# Teensy_Board_Connectors.net
KiCad netlist of a schematic drawn in EAGLE
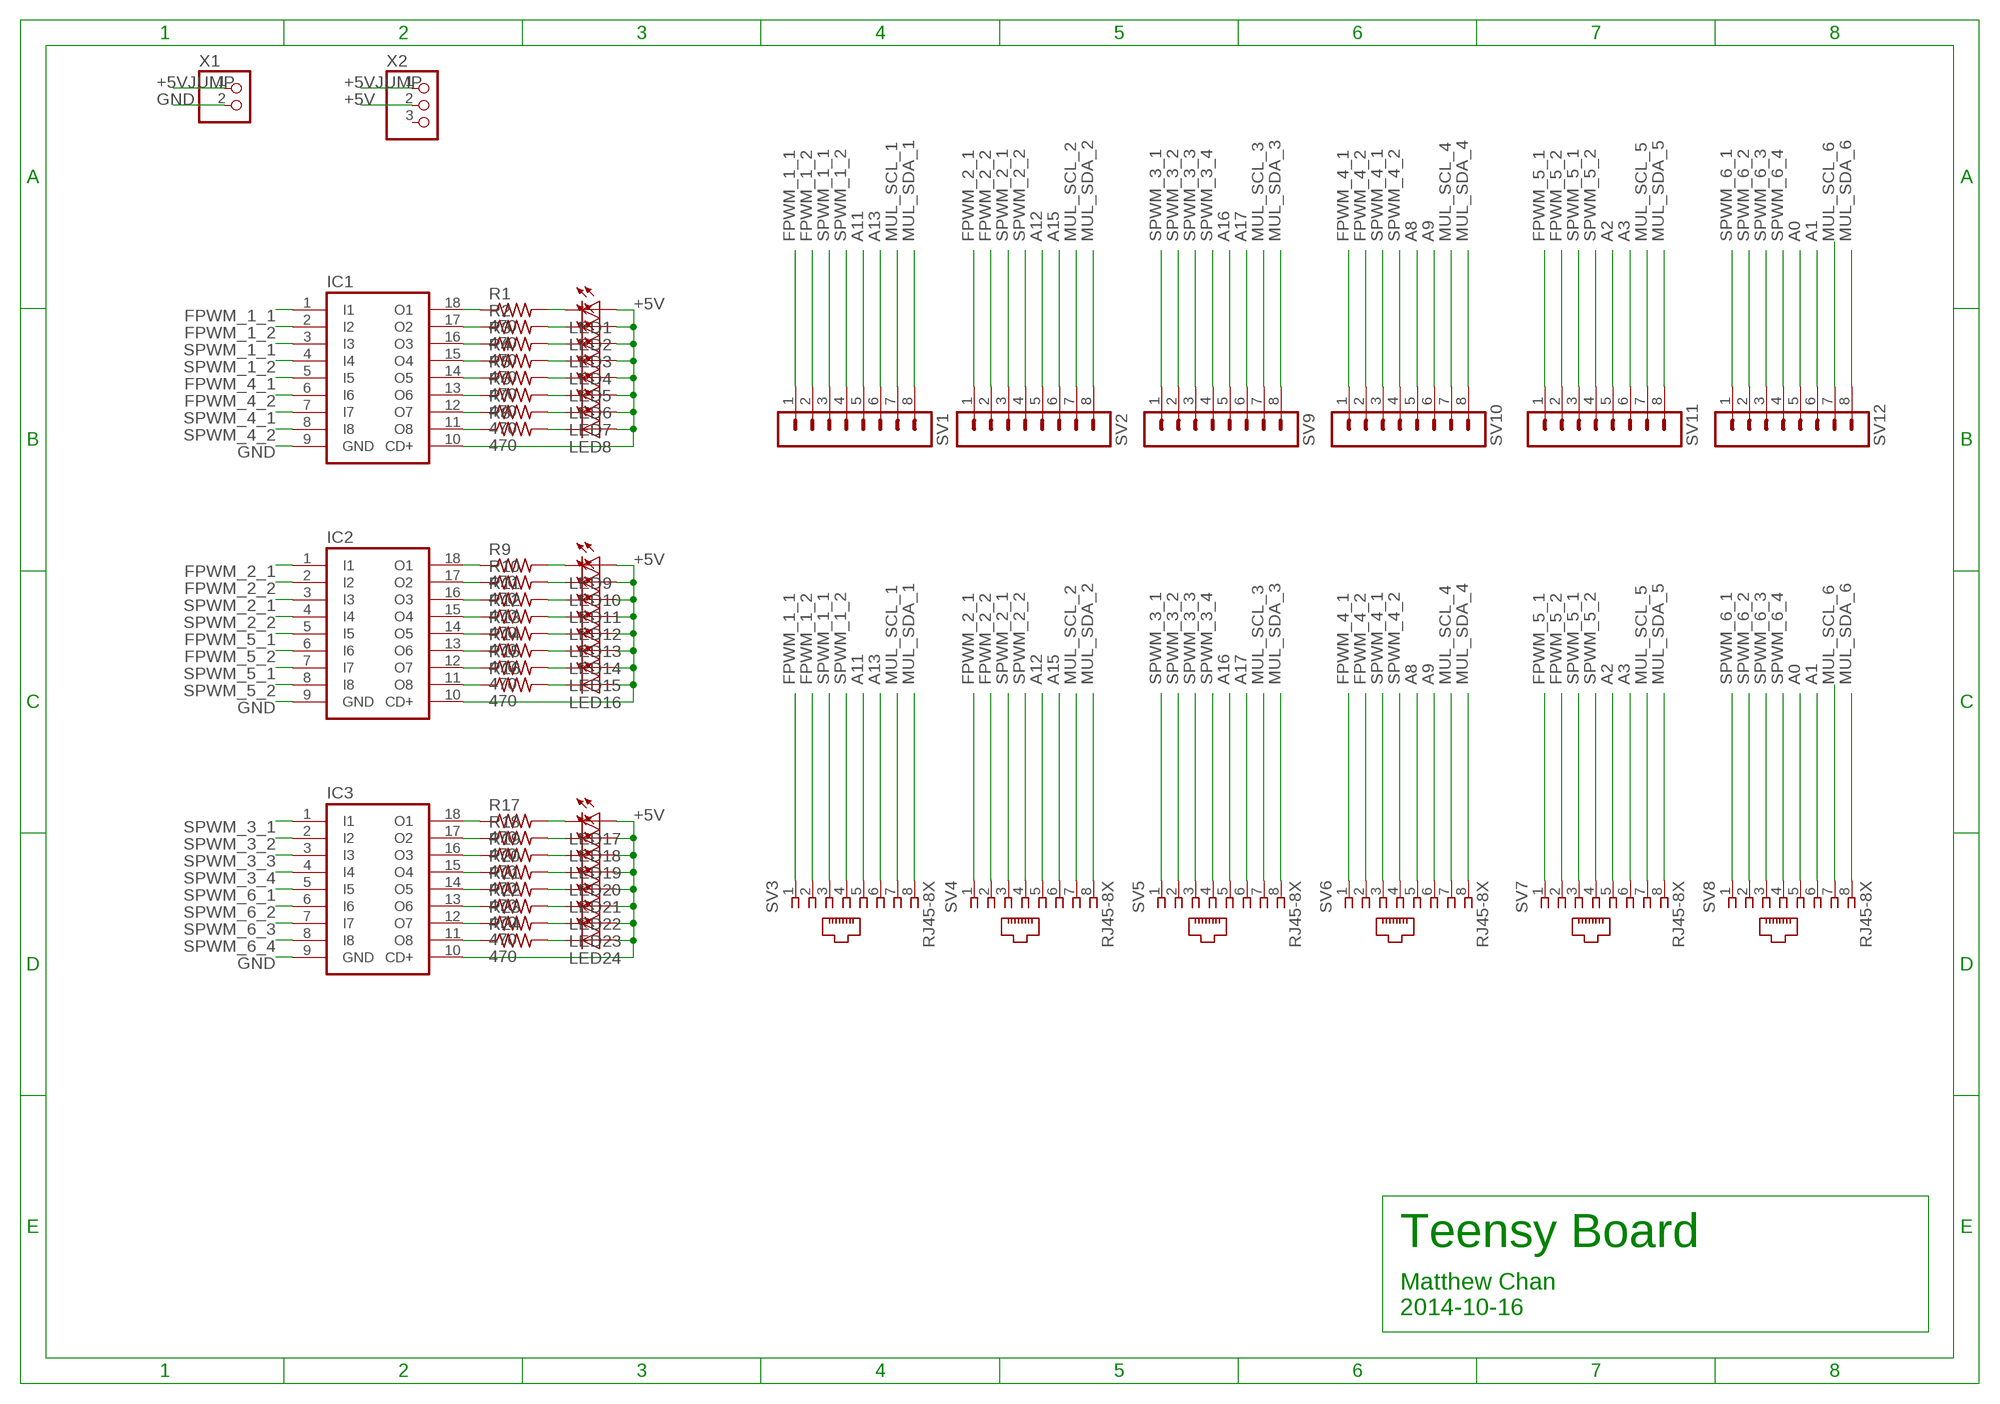
[diagram p0: schematic, sheet 1]

(export (version "E")
  (design (tool "Eeschema 10.0.6"))
  (components
    (comp (ref "IC1")
      (value "ULN2803AFWG")
      (footprint "eagle-import:SOP18")
      (libsource (lib "eagle-import") (part "ULN2803AFWG"))
    )
    (comp (ref "IC2")
      (value "ULN2803AFWG")
      (footprint "eagle-import:SOP18")
      (libsource (lib "eagle-import") (part "ULN2803AFWG"))
    )
    (comp (ref "IC3")
      (value "ULN2803AFWG")
      (footprint "eagle-import:SOP18")
      (libsource (lib "eagle-import") (part "ULN2803AFWG"))
    )
    (comp (ref "LED1")
      (value "LEDSML1206")
      (footprint "eagle-import:SML1206")
      (libsource (lib "eagle-import") (part "LEDSML1206"))
    )
    (comp (ref "LED2")
      (value "LEDSML1206")
      (footprint "eagle-import:SML1206")
      (libsource (lib "eagle-import") (part "LEDSML1206"))
    )
    (comp (ref "LED3")
      (value "LEDSML1206")
      (footprint "eagle-import:SML1206")
      (libsource (lib "eagle-import") (part "LEDSML1206"))
    )
    (comp (ref "LED4")
      (value "LEDSML1206")
      (footprint "eagle-import:SML1206")
      (libsource (lib "eagle-import") (part "LEDSML1206"))
    )
    (comp (ref "LED5")
      (value "LEDSML1206")
      (footprint "eagle-import:SML1206")
      (libsource (lib "eagle-import") (part "LEDSML1206"))
    )
    (comp (ref "LED6")
      (value "LEDSML1206")
      (footprint "eagle-import:SML1206")
      (libsource (lib "eagle-import") (part "LEDSML1206"))
    )
    (comp (ref "LED7")
      (value "LEDSML1206")
      (footprint "eagle-import:SML1206")
      (libsource (lib "eagle-import") (part "LEDSML1206"))
    )
    (comp (ref "LED8")
      (value "LEDSML1206")
      (footprint "eagle-import:SML1206")
      (libsource (lib "eagle-import") (part "LEDSML1206"))
    )
    (comp (ref "LED9")
      (value "LEDSML1206")
      (footprint "eagle-import:SML1206")
      (libsource (lib "eagle-import") (part "LEDSML1206"))
    )
    (comp (ref "LED10")
      (value "LEDSML1206")
      (footprint "eagle-import:SML1206")
      (libsource (lib "eagle-import") (part "LEDSML1206"))
    )
    (comp (ref "LED11")
      (value "LEDSML1206")
      (footprint "eagle-import:SML1206")
      (libsource (lib "eagle-import") (part "LEDSML1206"))
    )
    (comp (ref "LED12")
      (value "LEDSML1206")
      (footprint "eagle-import:SML1206")
      (libsource (lib "eagle-import") (part "LEDSML1206"))
    )
    (comp (ref "LED13")
      (value "LEDSML1206")
      (footprint "eagle-import:SML1206")
      (libsource (lib "eagle-import") (part "LEDSML1206"))
    )
    (comp (ref "LED14")
      (value "LEDSML1206")
      (footprint "eagle-import:SML1206")
      (libsource (lib "eagle-import") (part "LEDSML1206"))
    )
    (comp (ref "LED15")
      (value "LEDSML1206")
      (footprint "eagle-import:SML1206")
      (libsource (lib "eagle-import") (part "LEDSML1206"))
    )
    (comp (ref "LED16")
      (value "LEDSML1206")
      (footprint "eagle-import:SML1206")
      (libsource (lib "eagle-import") (part "LEDSML1206"))
    )
    (comp (ref "LED17")
      (value "LEDSML1206")
      (footprint "eagle-import:SML1206")
      (libsource (lib "eagle-import") (part "LEDSML1206"))
    )
    (comp (ref "LED18")
      (value "LEDSML1206")
      (footprint "eagle-import:SML1206")
      (libsource (lib "eagle-import") (part "LEDSML1206"))
    )
    (comp (ref "LED19")
      (value "LEDSML1206")
      (footprint "eagle-import:SML1206")
      (libsource (lib "eagle-import") (part "LEDSML1206"))
    )
    (comp (ref "LED20")
      (value "LEDSML1206")
      (footprint "eagle-import:SML1206")
      (libsource (lib "eagle-import") (part "LEDSML1206"))
    )
    (comp (ref "LED21")
      (value "LEDSML1206")
      (footprint "eagle-import:SML1206")
      (libsource (lib "eagle-import") (part "LEDSML1206"))
    )
    (comp (ref "LED22")
      (value "LEDSML1206")
      (footprint "eagle-import:SML1206")
      (libsource (lib "eagle-import") (part "LEDSML1206"))
    )
    (comp (ref "LED23")
      (value "LEDSML1206")
      (footprint "eagle-import:SML1206")
      (libsource (lib "eagle-import") (part "LEDSML1206"))
    )
    (comp (ref "LED24")
      (value "LEDSML1206")
      (footprint "eagle-import:SML1206")
      (libsource (lib "eagle-import") (part "LEDSML1206"))
    )
    (comp (ref "R1")
      (value "470")
      (footprint "eagle-import:R0603")
      (libsource (lib "eagle-import") (part "R-US_R0603"))
    )
    (comp (ref "R2")
      (value "470")
      (footprint "eagle-import:R0603")
      (libsource (lib "eagle-import") (part "R-US_R0603"))
    )
    (comp (ref "R3")
      (value "470")
      (footprint "eagle-import:R0603")
      (libsource (lib "eagle-import") (part "R-US_R0603"))
    )
    (comp (ref "R4")
      (value "470")
      (footprint "eagle-import:R0603")
      (libsource (lib "eagle-import") (part "R-US_R0603"))
    )
    (comp (ref "R5")
      (value "470")
      (footprint "eagle-import:R0603")
      (libsource (lib "eagle-import") (part "R-US_R0603"))
    )
    (comp (ref "R6")
      (value "470")
      (footprint "eagle-import:R0603")
      (libsource (lib "eagle-import") (part "R-US_R0603"))
    )
    (comp (ref "R7")
      (value "470")
      (footprint "eagle-import:R0603")
      (libsource (lib "eagle-import") (part "R-US_R0603"))
    )
    (comp (ref "R8")
      (value "470")
      (footprint "eagle-import:R0603")
      (libsource (lib "eagle-import") (part "R-US_R0603"))
    )
    (comp (ref "R9")
      (value "470")
      (footprint "eagle-import:R0603")
      (libsource (lib "eagle-import") (part "R-US_R0603"))
    )
    (comp (ref "R10")
      (value "470")
      (footprint "eagle-import:R0603")
      (libsource (lib "eagle-import") (part "R-US_R0603"))
    )
    (comp (ref "R11")
      (value "470")
      (footprint "eagle-import:R0603")
      (libsource (lib "eagle-import") (part "R-US_R0603"))
    )
    (comp (ref "R12")
      (value "470")
      (footprint "eagle-import:R0603")
      (libsource (lib "eagle-import") (part "R-US_R0603"))
    )
    (comp (ref "R13")
      (value "470")
      (footprint "eagle-import:R0603")
      (libsource (lib "eagle-import") (part "R-US_R0603"))
    )
    (comp (ref "R14")
      (value "470")
      (footprint "eagle-import:R0603")
      (libsource (lib "eagle-import") (part "R-US_R0603"))
    )
    (comp (ref "R15")
      (value "470")
      (footprint "eagle-import:R0603")
      (libsource (lib "eagle-import") (part "R-US_R0603"))
    )
    (comp (ref "R16")
      (value "470")
      (footprint "eagle-import:R0603")
      (libsource (lib "eagle-import") (part "R-US_R0603"))
    )
    (comp (ref "R17")
      (value "470")
      (footprint "eagle-import:R0603")
      (libsource (lib "eagle-import") (part "R-US_R0603"))
    )
    (comp (ref "R18")
      (value "470")
      (footprint "eagle-import:R0603")
      (libsource (lib "eagle-import") (part "R-US_R0603"))
    )
    (comp (ref "R19")
      (value "470")
      (footprint "eagle-import:R0603")
      (libsource (lib "eagle-import") (part "R-US_R0603"))
    )
    (comp (ref "R20")
      (value "470")
      (footprint "eagle-import:R0603")
      (libsource (lib "eagle-import") (part "R-US_R0603"))
    )
    (comp (ref "R21")
      (value "470")
      (footprint "eagle-import:R0603")
      (libsource (lib "eagle-import") (part "R-US_R0603"))
    )
    (comp (ref "R22")
      (value "470")
      (footprint "eagle-import:R0603")
      (libsource (lib "eagle-import") (part "R-US_R0603"))
    )
    (comp (ref "R23")
      (value "470")
      (footprint "eagle-import:R0603")
      (libsource (lib "eagle-import") (part "R-US_R0603"))
    )
    (comp (ref "R24")
      (value "470")
      (footprint "eagle-import:R0603")
      (libsource (lib "eagle-import") (part "R-US_R0603"))
    )
    (comp (ref "SV1")
      (value "MA08-1")
      (footprint "eagle-import:MA08-1")
      (libsource (lib "eagle-import") (part "MA08-1"))
    )
    (comp (ref "SV2")
      (value "MA08-1")
      (footprint "eagle-import:MA08-1")
      (libsource (lib "eagle-import") (part "MA08-1"))
    )
    (comp (ref "SV3")
      (value "RJ45-8X")
      (footprint "eagle-import:RJ45-NO-SHIELD")
      (libsource (lib "eagle-import") (part "RJ45-8X"))
    )
    (comp (ref "SV4")
      (value "RJ45-8X")
      (footprint "eagle-import:RJ45-NO-SHIELD")
      (libsource (lib "eagle-import") (part "RJ45-8X"))
    )
    (comp (ref "SV5")
      (value "RJ45-8X")
      (footprint "eagle-import:RJ45-NO-SHIELD")
      (libsource (lib "eagle-import") (part "RJ45-8X"))
    )
    (comp (ref "SV6")
      (value "RJ45-8X")
      (footprint "eagle-import:RJ45-NO-SHIELD")
      (libsource (lib "eagle-import") (part "RJ45-8X"))
    )
    (comp (ref "SV7")
      (value "RJ45-8X")
      (footprint "eagle-import:RJ45-NO-SHIELD")
      (libsource (lib "eagle-import") (part "RJ45-8X"))
    )
    (comp (ref "SV8")
      (value "RJ45-8X")
      (footprint "eagle-import:RJ45-NO-SHIELD")
      (libsource (lib "eagle-import") (part "RJ45-8X"))
    )
    (comp (ref "SV9")
      (value "MA08-1")
      (footprint "eagle-import:MA08-1")
      (libsource (lib "eagle-import") (part "MA08-1"))
    )
    (comp (ref "SV10")
      (value "MA08-1")
      (footprint "eagle-import:MA08-1")
      (libsource (lib "eagle-import") (part "MA08-1"))
    )
    (comp (ref "SV11")
      (value "MA08-1")
      (footprint "eagle-import:MA08-1")
      (libsource (lib "eagle-import") (part "MA08-1"))
    )
    (comp (ref "SV12")
      (value "MA08-1")
      (footprint "eagle-import:MA08-1")
      (libsource (lib "eagle-import") (part "MA08-1"))
    )
    (comp (ref "X1")
      (value "PINHD-1X2")
      (footprint "eagle-import:1X02")
      (libsource (lib "eagle-import") (part "PINHD-1X2"))
    )
    (comp (ref "X2")
      (value "PINHD-1X3")
      (footprint "eagle-import:1X03")
      (libsource (lib "eagle-import") (part "PINHD-1X3"))
    )
  )
  (nets
    (net (code "1") (name "/+5V") (class "Default")
      (node (ref "IC1") (pin "10") (pinfunction "CD+_10") (pintype "passive"))
      (node (ref "IC2") (pin "10") (pinfunction "CD+_10") (pintype "passive"))
      (node (ref "IC3") (pin "10") (pinfunction "CD+_10") (pintype "passive"))
      (node (ref "LED1") (pin "A") (pinfunction "A_A") (pintype "passive"))
      (node (ref "LED10") (pin "A") (pinfunction "A_A") (pintype "passive"))
      (node (ref "LED11") (pin "A") (pinfunction "A_A") (pintype "passive"))
      (node (ref "LED12") (pin "A") (pinfunction "A_A") (pintype "passive"))
      (node (ref "LED13") (pin "A") (pinfunction "A_A") (pintype "passive"))
      (node (ref "LED14") (pin "A") (pinfunction "A_A") (pintype "passive"))
      (node (ref "LED15") (pin "A") (pinfunction "A_A") (pintype "passive"))
      (node (ref "LED16") (pin "A") (pinfunction "A_A") (pintype "passive"))
      (node (ref "LED17") (pin "A") (pinfunction "A_A") (pintype "passive"))
      (node (ref "LED18") (pin "A") (pinfunction "A_A") (pintype "passive"))
      (node (ref "LED19") (pin "A") (pinfunction "A_A") (pintype "passive"))
      (node (ref "LED2") (pin "A") (pinfunction "A_A") (pintype "passive"))
      (node (ref "LED20") (pin "A") (pinfunction "A_A") (pintype "passive"))
      (node (ref "LED21") (pin "A") (pinfunction "A_A") (pintype "passive"))
      (node (ref "LED22") (pin "A") (pinfunction "A_A") (pintype "passive"))
      (node (ref "LED23") (pin "A") (pinfunction "A_A") (pintype "passive"))
      (node (ref "LED24") (pin "A") (pinfunction "A_A") (pintype "passive"))
      (node (ref "LED3") (pin "A") (pinfunction "A_A") (pintype "passive"))
      (node (ref "LED4") (pin "A") (pinfunction "A_A") (pintype "passive"))
      (node (ref "LED5") (pin "A") (pinfunction "A_A") (pintype "passive"))
      (node (ref "LED6") (pin "A") (pinfunction "A_A") (pintype "passive"))
      (node (ref "LED7") (pin "A") (pinfunction "A_A") (pintype "passive"))
      (node (ref "LED8") (pin "A") (pinfunction "A_A") (pintype "passive"))
      (node (ref "LED9") (pin "A") (pinfunction "A_A") (pintype "passive"))
      (node (ref "X2") (pin "2") (pinfunction "2_2") (pintype "passive"))
    )
    (net (code "2") (name "/+5VJUMP") (class "Default")
      (node (ref "X1") (pin "1") (pinfunction "1_1") (pintype "passive"))
      (node (ref "X2") (pin "1") (pinfunction "1_1") (pintype "passive"))
    )
    (net (code "3") (name "/A0") (class "Default")
      (node (ref "SV12") (pin "5") (pinfunction "5_5") (pintype "passive"))
      (node (ref "SV8") (pin "5") (pinfunction "5_5") (pintype "passive"))
    )
    (net (code "4") (name "/A1") (class "Default")
      (node (ref "SV12") (pin "6") (pinfunction "6_6") (pintype "passive"))
      (node (ref "SV8") (pin "6") (pinfunction "6_6") (pintype "passive"))
    )
    (net (code "5") (name "/A2") (class "Default")
      (node (ref "SV11") (pin "5") (pinfunction "5_5") (pintype "passive"))
      (node (ref "SV7") (pin "5") (pinfunction "5_5") (pintype "passive"))
    )
    (net (code "6") (name "/A3") (class "Default")
      (node (ref "SV11") (pin "6") (pinfunction "6_6") (pintype "passive"))
      (node (ref "SV7") (pin "6") (pinfunction "6_6") (pintype "passive"))
    )
    (net (code "7") (name "/A8") (class "Default")
      (node (ref "SV10") (pin "5") (pinfunction "5_5") (pintype "passive"))
      (node (ref "SV6") (pin "5") (pinfunction "5_5") (pintype "passive"))
    )
    (net (code "8") (name "/A9") (class "Default")
      (node (ref "SV10") (pin "6") (pinfunction "6_6") (pintype "passive"))
      (node (ref "SV6") (pin "6") (pinfunction "6_6") (pintype "passive"))
    )
    (net (code "9") (name "/A11") (class "Default")
      (node (ref "SV1") (pin "5") (pinfunction "5_5") (pintype "passive"))
      (node (ref "SV3") (pin "5") (pinfunction "5_5") (pintype "passive"))
    )
    (net (code "10") (name "/A12") (class "Default")
      (node (ref "SV2") (pin "5") (pinfunction "5_5") (pintype "passive"))
      (node (ref "SV4") (pin "5") (pinfunction "5_5") (pintype "passive"))
    )
    (net (code "11") (name "/A13") (class "Default")
      (node (ref "SV1") (pin "6") (pinfunction "6_6") (pintype "passive"))
      (node (ref "SV3") (pin "6") (pinfunction "6_6") (pintype "passive"))
    )
    (net (code "12") (name "/A15") (class "Default")
      (node (ref "SV2") (pin "6") (pinfunction "6_6") (pintype "passive"))
      (node (ref "SV4") (pin "6") (pinfunction "6_6") (pintype "passive"))
    )
    (net (code "13") (name "/A16") (class "Default")
      (node (ref "SV5") (pin "5") (pinfunction "5_5") (pintype "passive"))
      (node (ref "SV9") (pin "5") (pinfunction "5_5") (pintype "passive"))
    )
    (net (code "14") (name "/A17") (class "Default")
      (node (ref "SV5") (pin "6") (pinfunction "6_6") (pintype "passive"))
      (node (ref "SV9") (pin "6") (pinfunction "6_6") (pintype "passive"))
    )
    (net (code "15") (name "/FPWM_1_1") (class "Default")
      (node (ref "IC1") (pin "1") (pinfunction "I1_1") (pintype "input"))
      (node (ref "SV1") (pin "1") (pinfunction "1_1") (pintype "passive"))
      (node (ref "SV3") (pin "1") (pinfunction "1_1") (pintype "passive"))
    )
    (net (code "16") (name "/FPWM_1_2") (class "Default")
      (node (ref "IC1") (pin "2") (pinfunction "I2_2") (pintype "input"))
      (node (ref "SV1") (pin "2") (pinfunction "2_2") (pintype "passive"))
      (node (ref "SV3") (pin "2") (pinfunction "2_2") (pintype "passive"))
    )
    (net (code "17") (name "/FPWM_2_1") (class "Default")
      (node (ref "IC2") (pin "1") (pinfunction "I1_1") (pintype "input"))
      (node (ref "SV2") (pin "1") (pinfunction "1_1") (pintype "passive"))
      (node (ref "SV4") (pin "1") (pinfunction "1_1") (pintype "passive"))
    )
    (net (code "18") (name "/FPWM_2_2") (class "Default")
      (node (ref "IC2") (pin "2") (pinfunction "I2_2") (pintype "input"))
      (node (ref "SV2") (pin "2") (pinfunction "2_2") (pintype "passive"))
      (node (ref "SV4") (pin "2") (pinfunction "2_2") (pintype "passive"))
    )
    (net (code "19") (name "/FPWM_4_1") (class "Default")
      (node (ref "IC1") (pin "5") (pinfunction "I5_5") (pintype "input"))
      (node (ref "SV10") (pin "1") (pinfunction "1_1") (pintype "passive"))
      (node (ref "SV6") (pin "1") (pinfunction "1_1") (pintype "passive"))
    )
    (net (code "20") (name "/FPWM_4_2") (class "Default")
      (node (ref "IC1") (pin "6") (pinfunction "I6_6") (pintype "input"))
      (node (ref "SV10") (pin "2") (pinfunction "2_2") (pintype "passive"))
      (node (ref "SV6") (pin "2") (pinfunction "2_2") (pintype "passive"))
    )
    (net (code "21") (name "/FPWM_5_1") (class "Default")
      (node (ref "IC2") (pin "5") (pinfunction "I5_5") (pintype "input"))
      (node (ref "SV11") (pin "1") (pinfunction "1_1") (pintype "passive"))
      (node (ref "SV7") (pin "1") (pinfunction "1_1") (pintype "passive"))
    )
    (net (code "22") (name "/FPWM_5_2") (class "Default")
      (node (ref "IC2") (pin "6") (pinfunction "I6_6") (pintype "input"))
      (node (ref "SV11") (pin "2") (pinfunction "2_2") (pintype "passive"))
      (node (ref "SV7") (pin "2") (pinfunction "2_2") (pintype "passive"))
    )
    (net (code "23") (name "/GND") (class "Default")
      (node (ref "IC1") (pin "9") (pinfunction "GND_9") (pintype "power_in"))
      (node (ref "IC2") (pin "9") (pinfunction "GND_9") (pintype "power_in"))
      (node (ref "IC3") (pin "9") (pinfunction "GND_9") (pintype "power_in"))
      (node (ref "X1") (pin "2") (pinfunction "2_2") (pintype "passive"))
    )
    (net (code "24") (name "/MUL_SCL_1") (class "Default")
      (node (ref "SV1") (pin "7") (pinfunction "7_7") (pintype "passive"))
      (node (ref "SV3") (pin "7") (pinfunction "7_7") (pintype "passive"))
    )
    (net (code "25") (name "/MUL_SCL_2") (class "Default")
      (node (ref "SV2") (pin "7") (pinfunction "7_7") (pintype "passive"))
      (node (ref "SV4") (pin "7") (pinfunction "7_7") (pintype "passive"))
    )
    (net (code "26") (name "/MUL_SCL_3") (class "Default")
      (node (ref "SV5") (pin "7") (pinfunction "7_7") (pintype "passive"))
      (node (ref "SV9") (pin "7") (pinfunction "7_7") (pintype "passive"))
    )
    (net (code "27") (name "/MUL_SCL_4") (class "Default")
      (node (ref "SV10") (pin "7") (pinfunction "7_7") (pintype "passive"))
      (node (ref "SV6") (pin "7") (pinfunction "7_7") (pintype "passive"))
    )
    (net (code "28") (name "/MUL_SCL_5") (class "Default")
      (node (ref "SV11") (pin "7") (pinfunction "7_7") (pintype "passive"))
      (node (ref "SV7") (pin "7") (pinfunction "7_7") (pintype "passive"))
    )
    (net (code "29") (name "/MUL_SCL_6") (class "Default")
      (node (ref "SV12") (pin "7") (pinfunction "7_7") (pintype "passive"))
      (node (ref "SV8") (pin "7") (pinfunction "7_7") (pintype "passive"))
    )
    (net (code "30") (name "/MUL_SDA_1") (class "Default")
      (node (ref "SV1") (pin "8") (pinfunction "8_8") (pintype "passive"))
      (node (ref "SV3") (pin "8") (pinfunction "8_8") (pintype "passive"))
    )
    (net (code "31") (name "/MUL_SDA_2") (class "Default")
      (node (ref "SV2") (pin "8") (pinfunction "8_8") (pintype "passive"))
      (node (ref "SV4") (pin "8") (pinfunction "8_8") (pintype "passive"))
    )
    (net (code "32") (name "/MUL_SDA_3") (class "Default")
      (node (ref "SV5") (pin "8") (pinfunction "8_8") (pintype "passive"))
      (node (ref "SV9") (pin "8") (pinfunction "8_8") (pintype "passive"))
    )
    (net (code "33") (name "/MUL_SDA_4") (class "Default")
      (node (ref "SV10") (pin "8") (pinfunction "8_8") (pintype "passive"))
      (node (ref "SV6") (pin "8") (pinfunction "8_8") (pintype "passive"))
    )
    (net (code "34") (name "/MUL_SDA_5") (class "Default")
      (node (ref "SV11") (pin "8") (pinfunction "8_8") (pintype "passive"))
      (node (ref "SV7") (pin "8") (pinfunction "8_8") (pintype "passive"))
    )
    (net (code "35") (name "/MUL_SDA_6") (class "Default")
      (node (ref "SV12") (pin "8") (pinfunction "8_8") (pintype "passive"))
      (node (ref "SV8") (pin "8") (pinfunction "8_8") (pintype "passive"))
    )
    (net (code "36") (name "/SPWM_1_1") (class "Default")
      (node (ref "IC1") (pin "3") (pinfunction "I3_3") (pintype "input"))
      (node (ref "SV1") (pin "3") (pinfunction "3_3") (pintype "passive"))
      (node (ref "SV3") (pin "3") (pinfunction "3_3") (pintype "passive"))
    )
    (net (code "37") (name "/SPWM_1_2") (class "Default")
      (node (ref "IC1") (pin "4") (pinfunction "I4_4") (pintype "input"))
      (node (ref "SV1") (pin "4") (pinfunction "4_4") (pintype "passive"))
      (node (ref "SV3") (pin "4") (pinfunction "4_4") (pintype "passive"))
    )
    (net (code "38") (name "/SPWM_2_1") (class "Default")
      (node (ref "IC2") (pin "3") (pinfunction "I3_3") (pintype "input"))
      (node (ref "SV2") (pin "3") (pinfunction "3_3") (pintype "passive"))
      (node (ref "SV4") (pin "3") (pinfunction "3_3") (pintype "passive"))
    )
    (net (code "39") (name "/SPWM_2_2") (class "Default")
      (node (ref "IC2") (pin "4") (pinfunction "I4_4") (pintype "input"))
      (node (ref "SV2") (pin "4") (pinfunction "4_4") (pintype "passive"))
      (node (ref "SV4") (pin "4") (pinfunction "4_4") (pintype "passive"))
    )
    (net (code "40") (name "/SPWM_3_1") (class "Default")
      (node (ref "IC3") (pin "1") (pinfunction "I1_1") (pintype "input"))
      (node (ref "SV5") (pin "1") (pinfunction "1_1") (pintype "passive"))
      (node (ref "SV9") (pin "1") (pinfunction "1_1") (pintype "passive"))
    )
    (net (code "41") (name "/SPWM_3_2") (class "Default")
      (node (ref "IC3") (pin "2") (pinfunction "I2_2") (pintype "input"))
      (node (ref "SV5") (pin "2") (pinfunction "2_2") (pintype "passive"))
      (node (ref "SV9") (pin "2") (pinfunction "2_2") (pintype "passive"))
    )
    (net (code "42") (name "/SPWM_3_3") (class "Default")
      (node (ref "IC3") (pin "3") (pinfunction "I3_3") (pintype "input"))
      (node (ref "SV5") (pin "3") (pinfunction "3_3") (pintype "passive"))
      (node (ref "SV9") (pin "3") (pinfunction "3_3") (pintype "passive"))
    )
    (net (code "43") (name "/SPWM_3_4") (class "Default")
      (node (ref "IC3") (pin "4") (pinfunction "I4_4") (pintype "input"))
      (node (ref "SV5") (pin "4") (pinfunction "4_4") (pintype "passive"))
      (node (ref "SV9") (pin "4") (pinfunction "4_4") (pintype "passive"))
    )
    (net (code "44") (name "/SPWM_4_1") (class "Default")
      (node (ref "IC1") (pin "7") (pinfunction "I7_7") (pintype "input"))
      (node (ref "SV10") (pin "3") (pinfunction "3_3") (pintype "passive"))
      (node (ref "SV6") (pin "3") (pinfunction "3_3") (pintype "passive"))
    )
    (net (code "45") (name "/SPWM_4_2") (class "Default")
      (node (ref "IC1") (pin "8") (pinfunction "I8_8") (pintype "input"))
      (node (ref "SV10") (pin "4") (pinfunction "4_4") (pintype "passive"))
      (node (ref "SV6") (pin "4") (pinfunction "4_4") (pintype "passive"))
    )
    (net (code "46") (name "/SPWM_5_1") (class "Default")
      (node (ref "IC2") (pin "7") (pinfunction "I7_7") (pintype "input"))
      (node (ref "SV11") (pin "3") (pinfunction "3_3") (pintype "passive"))
      (node (ref "SV7") (pin "3") (pinfunction "3_3") (pintype "passive"))
    )
    (net (code "47") (name "/SPWM_5_2") (class "Default")
      (node (ref "IC2") (pin "8") (pinfunction "I8_8") (pintype "input"))
      (node (ref "SV11") (pin "4") (pinfunction "4_4") (pintype "passive"))
      (node (ref "SV7") (pin "4") (pinfunction "4_4") (pintype "passive"))
    )
    (net (code "48") (name "/SPWM_6_1") (class "Default")
      (node (ref "IC3") (pin "5") (pinfunction "I5_5") (pintype "input"))
      (node (ref "SV12") (pin "1") (pinfunction "1_1") (pintype "passive"))
      (node (ref "SV8") (pin "1") (pinfunction "1_1") (pintype "passive"))
    )
    (net (code "49") (name "/SPWM_6_2") (class "Default")
      (node (ref "IC3") (pin "6") (pinfunction "I6_6") (pintype "input"))
      (node (ref "SV12") (pin "2") (pinfunction "2_2") (pintype "passive"))
      (node (ref "SV8") (pin "2") (pinfunction "2_2") (pintype "passive"))
    )
    (net (code "50") (name "/SPWM_6_3") (class "Default")
      (node (ref "IC3") (pin "7") (pinfunction "I7_7") (pintype "input"))
      (node (ref "SV12") (pin "3") (pinfunction "3_3") (pintype "passive"))
      (node (ref "SV8") (pin "3") (pinfunction "3_3") (pintype "passive"))
    )
    (net (code "51") (name "/SPWM_6_4") (class "Default")
      (node (ref "IC3") (pin "8") (pinfunction "I8_8") (pintype "input"))
      (node (ref "SV12") (pin "4") (pinfunction "4_4") (pintype "passive"))
      (node (ref "SV8") (pin "4") (pinfunction "4_4") (pintype "passive"))
    )
    (net (code "52") (name "Net-(IC1-O1)") (class "Default")
      (node (ref "IC1") (pin "18") (pinfunction "O1_18") (pintype "open_collector"))
      (node (ref "R1") (pin "1") (pinfunction "1_1") (pintype "passive"))
    )
    (net (code "53") (name "Net-(IC1-O2)") (class "Default")
      (node (ref "IC1") (pin "17") (pinfunction "O2_17") (pintype "open_collector"))
      (node (ref "R2") (pin "1") (pinfunction "1_1") (pintype "passive"))
    )
    (net (code "54") (name "Net-(IC1-O3)") (class "Default")
      (node (ref "IC1") (pin "16") (pinfunction "O3_16") (pintype "open_collector"))
      (node (ref "R3") (pin "1") (pinfunction "1_1") (pintype "passive"))
    )
    (net (code "55") (name "Net-(IC1-O4)") (class "Default")
      (node (ref "IC1") (pin "15") (pinfunction "O4_15") (pintype "open_collector"))
      (node (ref "R4") (pin "1") (pinfunction "1_1") (pintype "passive"))
    )
    (net (code "56") (name "Net-(IC1-O5)") (class "Default")
      (node (ref "IC1") (pin "14") (pinfunction "O5_14") (pintype "open_collector"))
      (node (ref "R5") (pin "1") (pinfunction "1_1") (pintype "passive"))
    )
    (net (code "57") (name "Net-(IC1-O6)") (class "Default")
      (node (ref "IC1") (pin "13") (pinfunction "O6_13") (pintype "open_collector"))
      (node (ref "R6") (pin "1") (pinfunction "1_1") (pintype "passive"))
    )
    (net (code "58") (name "Net-(IC1-O7)") (class "Default")
      (node (ref "IC1") (pin "12") (pinfunction "O7_12") (pintype "open_collector"))
      (node (ref "R7") (pin "1") (pinfunction "1_1") (pintype "passive"))
    )
    (net (code "59") (name "Net-(IC1-O8)") (class "Default")
      (node (ref "IC1") (pin "11") (pinfunction "O8_11") (pintype "open_collector"))
      (node (ref "R8") (pin "1") (pinfunction "1_1") (pintype "passive"))
    )
    (net (code "60") (name "Net-(IC2-O1)") (class "Default")
      (node (ref "IC2") (pin "18") (pinfunction "O1_18") (pintype "open_collector"))
      (node (ref "R9") (pin "1") (pinfunction "1_1") (pintype "passive"))
    )
    (net (code "61") (name "Net-(IC2-O2)") (class "Default")
      (node (ref "IC2") (pin "17") (pinfunction "O2_17") (pintype "open_collector"))
      (node (ref "R10") (pin "1") (pinfunction "1_1") (pintype "passive"))
    )
    (net (code "62") (name "Net-(IC2-O3)") (class "Default")
      (node (ref "IC2") (pin "16") (pinfunction "O3_16") (pintype "open_collector"))
      (node (ref "R11") (pin "1") (pinfunction "1_1") (pintype "passive"))
    )
    (net (code "63") (name "Net-(IC2-O4)") (class "Default")
      (node (ref "IC2") (pin "15") (pinfunction "O4_15") (pintype "open_collector"))
      (node (ref "R12") (pin "1") (pinfunction "1_1") (pintype "passive"))
    )
    (net (code "64") (name "Net-(IC2-O5)") (class "Default")
      (node (ref "IC2") (pin "14") (pinfunction "O5_14") (pintype "open_collector"))
      (node (ref "R13") (pin "1") (pinfunction "1_1") (pintype "passive"))
    )
    (net (code "65") (name "Net-(IC2-O6)") (class "Default")
      (node (ref "IC2") (pin "13") (pinfunction "O6_13") (pintype "open_collector"))
      (node (ref "R14") (pin "1") (pinfunction "1_1") (pintype "passive"))
    )
    (net (code "66") (name "Net-(IC2-O7)") (class "Default")
      (node (ref "IC2") (pin "12") (pinfunction "O7_12") (pintype "open_collector"))
      (node (ref "R15") (pin "1") (pinfunction "1_1") (pintype "passive"))
    )
    (net (code "67") (name "Net-(IC2-O8)") (class "Default")
      (node (ref "IC2") (pin "11") (pinfunction "O8_11") (pintype "open_collector"))
      (node (ref "R16") (pin "1") (pinfunction "1_1") (pintype "passive"))
    )
    (net (code "68") (name "Net-(IC3-O1)") (class "Default")
      (node (ref "IC3") (pin "18") (pinfunction "O1_18") (pintype "open_collector"))
      (node (ref "R17") (pin "1") (pinfunction "1_1") (pintype "passive"))
    )
    (net (code "69") (name "Net-(IC3-O2)") (class "Default")
      (node (ref "IC3") (pin "17") (pinfunction "O2_17") (pintype "open_collector"))
      (node (ref "R18") (pin "1") (pinfunction "1_1") (pintype "passive"))
    )
    (net (code "70") (name "Net-(IC3-O3)") (class "Default")
      (node (ref "IC3") (pin "16") (pinfunction "O3_16") (pintype "open_collector"))
      (node (ref "R19") (pin "1") (pinfunction "1_1") (pintype "passive"))
    )
    (net (code "71") (name "Net-(IC3-O4)") (class "Default")
      (node (ref "IC3") (pin "15") (pinfunction "O4_15") (pintype "open_collector"))
      (node (ref "R20") (pin "1") (pinfunction "1_1") (pintype "passive"))
    )
    (net (code "72") (name "Net-(IC3-O5)") (class "Default")
      (node (ref "IC3") (pin "14") (pinfunction "O5_14") (pintype "open_collector"))
      (node (ref "R21") (pin "1") (pinfunction "1_1") (pintype "passive"))
    )
    (net (code "73") (name "Net-(IC3-O6)") (class "Default")
      (node (ref "IC3") (pin "13") (pinfunction "O6_13") (pintype "open_collector"))
      (node (ref "R22") (pin "1") (pinfunction "1_1") (pintype "passive"))
    )
    (net (code "74") (name "Net-(IC3-O7)") (class "Default")
      (node (ref "IC3") (pin "12") (pinfunction "O7_12") (pintype "open_collector"))
      (node (ref "R23") (pin "1") (pinfunction "1_1") (pintype "passive"))
    )
    (net (code "75") (name "Net-(IC3-O8)") (class "Default")
      (node (ref "IC3") (pin "11") (pinfunction "O8_11") (pintype "open_collector"))
      (node (ref "R24") (pin "1") (pinfunction "1_1") (pintype "passive"))
    )
    (net (code "76") (name "Net-(LED1-PadC)") (class "Default")
      (node (ref "LED1") (pin "C") (pinfunction "C_C") (pintype "passive"))
      (node (ref "R1") (pin "2") (pinfunction "2_2") (pintype "passive"))
    )
    (net (code "77") (name "Net-(LED2-PadC)") (class "Default")
      (node (ref "LED2") (pin "C") (pinfunction "C_C") (pintype "passive"))
      (node (ref "R2") (pin "2") (pinfunction "2_2") (pintype "passive"))
    )
    (net (code "78") (name "Net-(LED3-PadC)") (class "Default")
      (node (ref "LED3") (pin "C") (pinfunction "C_C") (pintype "passive"))
      (node (ref "R3") (pin "2") (pinfunction "2_2") (pintype "passive"))
    )
    (net (code "79") (name "Net-(LED4-PadC)") (class "Default")
      (node (ref "LED4") (pin "C") (pinfunction "C_C") (pintype "passive"))
      (node (ref "R4") (pin "2") (pinfunction "2_2") (pintype "passive"))
    )
    (net (code "80") (name "Net-(LED5-PadC)") (class "Default")
      (node (ref "LED5") (pin "C") (pinfunction "C_C") (pintype "passive"))
      (node (ref "R5") (pin "2") (pinfunction "2_2") (pintype "passive"))
    )
    (net (code "81") (name "Net-(LED6-PadC)") (class "Default")
      (node (ref "LED6") (pin "C") (pinfunction "C_C") (pintype "passive"))
      (node (ref "R6") (pin "2") (pinfunction "2_2") (pintype "passive"))
    )
    (net (code "82") (name "Net-(LED7-PadC)") (class "Default")
      (node (ref "LED7") (pin "C") (pinfunction "C_C") (pintype "passive"))
      (node (ref "R7") (pin "2") (pinfunction "2_2") (pintype "passive"))
    )
    (net (code "83") (name "Net-(LED8-PadC)") (class "Default")
      (node (ref "LED8") (pin "C") (pinfunction "C_C") (pintype "passive"))
      (node (ref "R8") (pin "2") (pinfunction "2_2") (pintype "passive"))
    )
    (net (code "84") (name "Net-(LED9-PadC)") (class "Default")
      (node (ref "LED9") (pin "C") (pinfunction "C_C") (pintype "passive"))
      (node (ref "R9") (pin "2") (pinfunction "2_2") (pintype "passive"))
    )
    (net (code "85") (name "Net-(LED10-PadC)") (class "Default")
      (node (ref "LED10") (pin "C") (pinfunction "C_C") (pintype "passive"))
      (node (ref "R10") (pin "2") (pinfunction "2_2") (pintype "passive"))
    )
    (net (code "86") (name "Net-(LED11-PadC)") (class "Default")
      (node (ref "LED11") (pin "C") (pinfunction "C_C") (pintype "passive"))
      (node (ref "R11") (pin "2") (pinfunction "2_2") (pintype "passive"))
    )
    (net (code "87") (name "Net-(LED12-PadC)") (class "Default")
      (node (ref "LED12") (pin "C") (pinfunction "C_C") (pintype "passive"))
      (node (ref "R12") (pin "2") (pinfunction "2_2") (pintype "passive"))
    )
    (net (code "88") (name "Net-(LED13-PadC)") (class "Default")
      (node (ref "LED13") (pin "C") (pinfunction "C_C") (pintype "passive"))
      (node (ref "R13") (pin "2") (pinfunction "2_2") (pintype "passive"))
    )
    (net (code "89") (name "Net-(LED14-PadC)") (class "Default")
      (node (ref "LED14") (pin "C") (pinfunction "C_C") (pintype "passive"))
      (node (ref "R14") (pin "2") (pinfunction "2_2") (pintype "passive"))
    )
    (net (code "90") (name "Net-(LED15-PadC)") (class "Default")
      (node (ref "LED15") (pin "C") (pinfunction "C_C") (pintype "passive"))
      (node (ref "R15") (pin "2") (pinfunction "2_2") (pintype "passive"))
    )
    (net (code "91") (name "Net-(LED16-PadC)") (class "Default")
      (node (ref "LED16") (pin "C") (pinfunction "C_C") (pintype "passive"))
      (node (ref "R16") (pin "2") (pinfunction "2_2") (pintype "passive"))
    )
    (net (code "92") (name "Net-(LED17-PadC)") (class "Default")
      (node (ref "LED17") (pin "C") (pinfunction "C_C") (pintype "passive"))
      (node (ref "R17") (pin "2") (pinfunction "2_2") (pintype "passive"))
    )
    (net (code "93") (name "Net-(LED18-PadC)") (class "Default")
      (node (ref "LED18") (pin "C") (pinfunction "C_C") (pintype "passive"))
      (node (ref "R18") (pin "2") (pinfunction "2_2") (pintype "passive"))
    )
    (net (code "94") (name "Net-(LED19-PadC)") (class "Default")
      (node (ref "LED19") (pin "C") (pinfunction "C_C") (pintype "passive"))
      (node (ref "R19") (pin "2") (pinfunction "2_2") (pintype "passive"))
    )
    (net (code "95") (name "Net-(LED20-PadC)") (class "Default")
      (node (ref "LED20") (pin "C") (pinfunction "C_C") (pintype "passive"))
      (node (ref "R20") (pin "2") (pinfunction "2_2") (pintype "passive"))
    )
    (net (code "96") (name "Net-(LED21-PadC)") (class "Default")
      (node (ref "LED21") (pin "C") (pinfunction "C_C") (pintype "passive"))
      (node (ref "R21") (pin "2") (pinfunction "2_2") (pintype "passive"))
    )
    (net (code "97") (name "Net-(LED22-PadC)") (class "Default")
      (node (ref "LED22") (pin "C") (pinfunction "C_C") (pintype "passive"))
      (node (ref "R22") (pin "2") (pinfunction "2_2") (pintype "passive"))
    )
    (net (code "98") (name "Net-(LED23-PadC)") (class "Default")
      (node (ref "LED23") (pin "C") (pinfunction "C_C") (pintype "passive"))
      (node (ref "R23") (pin "2") (pinfunction "2_2") (pintype "passive"))
    )
    (net (code "99") (name "Net-(LED24-PadC)") (class "Default")
      (node (ref "LED24") (pin "C") (pinfunction "C_C") (pintype "passive"))
      (node (ref "R24") (pin "2") (pinfunction "2_2") (pintype "passive"))
    )
    (net (code "100") (name "unconnected-(X2-Pad3)") (class "Default")
      (node (ref "X2") (pin "3") (pinfunction "3_3") (pintype "passive"))
    )
  )
)
